# kbd.net
KiCad netlist of a schematic drawn in EAGLE
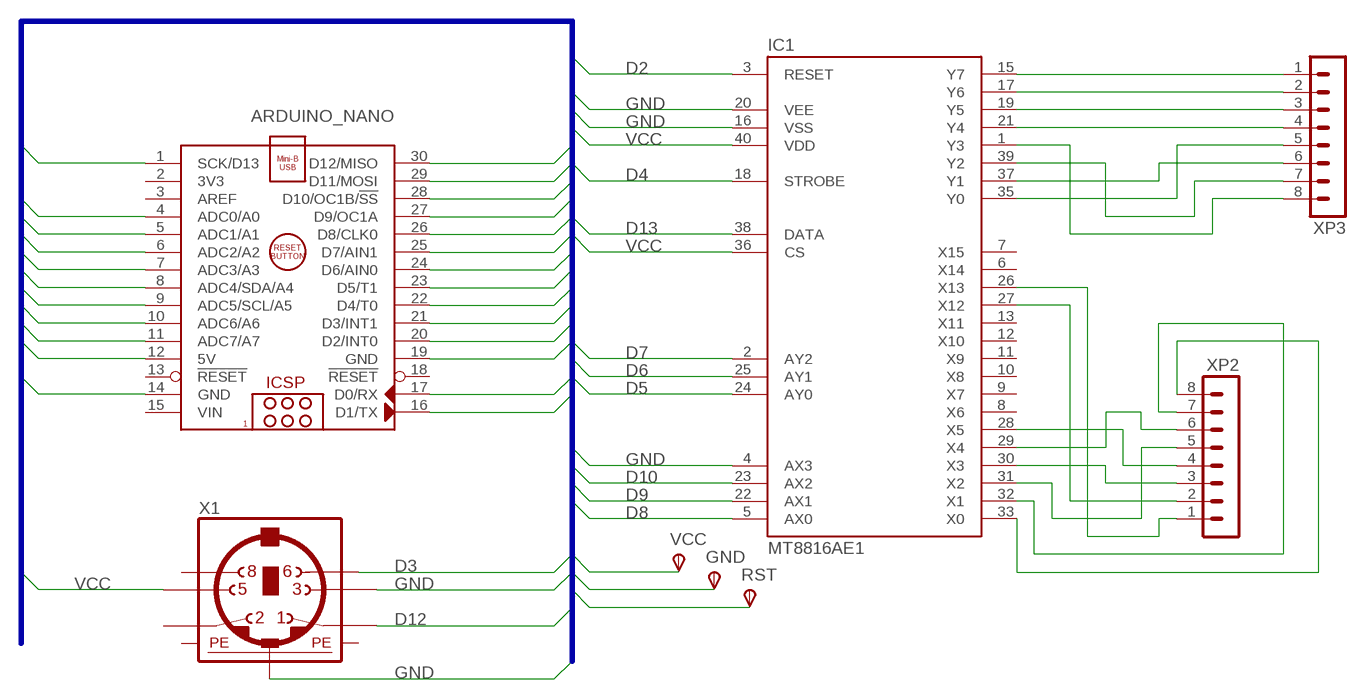
[diagram p0: schematic, sheet 1]

(export (version "E")
  (design (tool "Eeschema 10.0.6"))
  (components
    (comp (ref "ARDUINO_NANO")
      (value "ARDUINO_NANO")
      (footprint "eagle-import:ARDUINO_NANO")
      (libsource (lib "eagle-import") (part "ARDUINO_NANO"))
    )
    (comp (ref "GND")
      (value "TPSPAD1-13")
      (footprint "eagle-import:P1-13")
      (libsource (lib "eagle-import") (part "TPSPAD1-13"))
    )
    (comp (ref "IC1")
      (value "MT8816AE1")
      (footprint "eagle-import:DIL40")
      (libsource (lib "eagle-import") (part "MT8816AE1"))
    )
    (comp (ref "RST")
      (value "TPSPAD1-13")
      (footprint "eagle-import:P1-13")
      (libsource (lib "eagle-import") (part "TPSPAD1-13"))
    )
    (comp (ref "VCC")
      (value "TPSPAD1-13")
      (footprint "eagle-import:P1-13")
      (libsource (lib "eagle-import") (part "TPSPAD1-13"))
    )
    (comp (ref "X1")
      (value "MINI_DIN_6")
      (footprint "eagle-import:M_DIN6")
      (libsource (lib "eagle-import") (part "MINI_DIN_6"))
    )
    (comp (ref "XP2")
      (value "MA08-1")
      (footprint "eagle-import:MA08-1")
      (libsource (lib "eagle-import") (part "MA08-1"))
    )
    (comp (ref "XP3")
      (value "MA08-1")
      (footprint "eagle-import:MA08-1")
      (libsource (lib "eagle-import") (part "MA08-1"))
    )
  )
  (nets
    (net (code "1") (name "/A0") (class "Default")
      (node (ref "ARDUINO_NANO") (pin "4") (pinfunction "ADC0/A0_4") (pintype "bidirectional"))
      (node (ref "RST") (pin "TP") (pinfunction "PP_TP") (pintype "input"))
    )
    (net (code "2") (name "/D2") (class "Default")
      (node (ref "ARDUINO_NANO") (pin "20") (pinfunction "D2/INT0_20") (pintype "bidirectional"))
      (node (ref "IC1") (pin "3") (pinfunction "RESET_3") (pintype "input"))
    )
    (net (code "3") (name "/D3") (class "Default")
      (node (ref "ARDUINO_NANO") (pin "21") (pinfunction "D3/INT1_21") (pintype "bidirectional"))
      (node (ref "X1") (pin "6") (pinfunction "6_6") (pintype "passive"))
    )
    (net (code "4") (name "/D4") (class "Default")
      (node (ref "ARDUINO_NANO") (pin "22") (pinfunction "D4/T0_22") (pintype "bidirectional"))
      (node (ref "IC1") (pin "18") (pinfunction "STROBE_18") (pintype "input"))
    )
    (net (code "5") (name "/D5") (class "Default")
      (node (ref "ARDUINO_NANO") (pin "23") (pinfunction "D5/T1_23") (pintype "bidirectional"))
      (node (ref "IC1") (pin "24") (pinfunction "AY0_24") (pintype "input"))
    )
    (net (code "6") (name "/D6") (class "Default")
      (node (ref "ARDUINO_NANO") (pin "24") (pinfunction "D6/AIN0_24") (pintype "bidirectional"))
      (node (ref "IC1") (pin "25") (pinfunction "AY1_25") (pintype "input"))
    )
    (net (code "7") (name "/D7") (class "Default")
      (node (ref "ARDUINO_NANO") (pin "25") (pinfunction "D7/AIN1_25") (pintype "bidirectional"))
      (node (ref "IC1") (pin "2") (pinfunction "AY2_2") (pintype "input"))
    )
    (net (code "8") (name "/D8") (class "Default")
      (node (ref "ARDUINO_NANO") (pin "26") (pinfunction "D8/CLK0_26") (pintype "bidirectional"))
      (node (ref "IC1") (pin "5") (pinfunction "AX0_5") (pintype "input"))
    )
    (net (code "9") (name "/D9") (class "Default")
      (node (ref "ARDUINO_NANO") (pin "27") (pinfunction "D9/OC1A_27") (pintype "bidirectional"))
      (node (ref "IC1") (pin "22") (pinfunction "AX1_22") (pintype "input"))
    )
    (net (code "10") (name "/D10") (class "Default")
      (node (ref "ARDUINO_NANO") (pin "28") (pinfunction "D10/OC1B/~{SS}_28") (pintype "bidirectional"))
      (node (ref "IC1") (pin "23") (pinfunction "AX2_23") (pintype "input"))
    )
    (net (code "11") (name "/D12") (class "Default")
      (node (ref "ARDUINO_NANO") (pin "30") (pinfunction "D12/MISO_30") (pintype "bidirectional"))
      (node (ref "X1") (pin "1") (pinfunction "1_1") (pintype "passive"))
    )
    (net (code "12") (name "/D13") (class "Default")
      (node (ref "ARDUINO_NANO") (pin "1") (pinfunction "SCK/D13_1") (pintype "bidirectional"))
      (node (ref "IC1") (pin "38") (pinfunction "DATA_38") (pintype "input"))
    )
    (net (code "13") (name "/GND") (class "Default")
      (node (ref "ARDUINO_NANO") (pin "14") (pinfunction "GND_14") (pintype "power_in"))
      (node (ref "ARDUINO_NANO") (pin "19") (pinfunction "GND_19") (pintype "power_in"))
      (node (ref "GND") (pin "TP") (pinfunction "PP_TP") (pintype "input"))
      (node (ref "IC1") (pin "16") (pinfunction "VSS_16") (pintype "power_in"))
      (node (ref "IC1") (pin "20") (pinfunction "VEE_20") (pintype "power_in"))
      (node (ref "IC1") (pin "4") (pinfunction "AX3_4") (pintype "input"))
      (node (ref "X1") (pin "3") (pinfunction "3_3") (pintype "passive"))
      (node (ref "X1") (pin "SH2") (pinfunction "PE2_SH2") (pintype "power_in"))
    )
    (net (code "14") (name "/PE1") (class "Default")
      (node (ref "X1") (pin "SH1") (pinfunction "PE1_SH1") (pintype "power_in"))
    )
    (net (code "15") (name "/PE3") (class "Default")
      (node (ref "X1") (pin "SH3") (pinfunction "PE3_SH3") (pintype "power_in"))
    )
    (net (code "16") (name "/VCC") (class "Default")
      (node (ref "ARDUINO_NANO") (pin "12") (pinfunction "5V_12") (pintype "power_in"))
      (node (ref "IC1") (pin "36") (pinfunction "CS_36") (pintype "input"))
      (node (ref "IC1") (pin "40") (pinfunction "VDD_40") (pintype "power_in"))
      (node (ref "VCC") (pin "TP") (pinfunction "PP_TP") (pintype "input"))
      (node (ref "X1") (pin "5") (pinfunction "5_5") (pintype "passive"))
    )
    (net (code "17") (name "/VIN") (class "Default")
      (node (ref "ARDUINO_NANO") (pin "15") (pinfunction "VIN_15") (pintype "power_in"))
    )
    (net (code "18") (name "Net-(IC1-X0)") (class "Default")
      (node (ref "IC1") (pin "33") (pinfunction "X0_33") (pintype "bidirectional"))
      (node (ref "XP2") (pin "8") (pinfunction "8_8") (pintype "passive"))
    )
    (net (code "19") (name "Net-(IC1-X1)") (class "Default")
      (node (ref "IC1") (pin "32") (pinfunction "X1_32") (pintype "bidirectional"))
      (node (ref "XP2") (pin "7") (pinfunction "7_7") (pintype "passive"))
    )
    (net (code "20") (name "Net-(IC1-X2)") (class "Default")
      (node (ref "IC1") (pin "31") (pinfunction "X2_31") (pintype "bidirectional"))
      (node (ref "XP2") (pin "5") (pinfunction "5_5") (pintype "passive"))
    )
    (net (code "21") (name "Net-(IC1-X3)") (class "Default")
      (node (ref "IC1") (pin "30") (pinfunction "X3_30") (pintype "bidirectional"))
      (node (ref "XP2") (pin "3") (pinfunction "3_3") (pintype "passive"))
    )
    (net (code "22") (name "Net-(IC1-X4)") (class "Default")
      (node (ref "IC1") (pin "29") (pinfunction "X4_29") (pintype "bidirectional"))
      (node (ref "XP2") (pin "6") (pinfunction "6_6") (pintype "passive"))
    )
    (net (code "23") (name "Net-(IC1-X5)") (class "Default")
      (node (ref "IC1") (pin "28") (pinfunction "X5_28") (pintype "bidirectional"))
      (node (ref "XP2") (pin "4") (pinfunction "4_4") (pintype "passive"))
    )
    (net (code "24") (name "Net-(IC1-X12)") (class "Default")
      (node (ref "IC1") (pin "27") (pinfunction "X12_27") (pintype "bidirectional"))
      (node (ref "XP2") (pin "2") (pinfunction "2_2") (pintype "passive"))
    )
    (net (code "25") (name "Net-(IC1-X13)") (class "Default")
      (node (ref "IC1") (pin "26") (pinfunction "X13_26") (pintype "bidirectional"))
      (node (ref "XP2") (pin "1") (pinfunction "1_1") (pintype "passive"))
    )
    (net (code "26") (name "Net-(IC1-Y0)") (class "Default")
      (node (ref "IC1") (pin "35") (pinfunction "Y0_35") (pintype "bidirectional"))
      (node (ref "XP3") (pin "5") (pinfunction "5_5") (pintype "passive"))
    )
    (net (code "27") (name "Net-(IC1-Y1)") (class "Default")
      (node (ref "IC1") (pin "37") (pinfunction "Y1_37") (pintype "bidirectional"))
      (node (ref "XP3") (pin "6") (pinfunction "6_6") (pintype "passive"))
    )
    (net (code "28") (name "Net-(IC1-Y2)") (class "Default")
      (node (ref "IC1") (pin "39") (pinfunction "Y2_39") (pintype "bidirectional"))
      (node (ref "XP3") (pin "7") (pinfunction "7_7") (pintype "passive"))
    )
    (net (code "29") (name "Net-(IC1-Y3)") (class "Default")
      (node (ref "IC1") (pin "1") (pinfunction "Y3_1") (pintype "bidirectional"))
      (node (ref "XP3") (pin "8") (pinfunction "8_8") (pintype "passive"))
    )
    (net (code "30") (name "Net-(IC1-Y4)") (class "Default")
      (node (ref "IC1") (pin "21") (pinfunction "Y4_21") (pintype "bidirectional"))
      (node (ref "XP3") (pin "4") (pinfunction "4_4") (pintype "passive"))
    )
    (net (code "31") (name "Net-(IC1-Y5)") (class "Default")
      (node (ref "IC1") (pin "19") (pinfunction "Y5_19") (pintype "bidirectional"))
      (node (ref "XP3") (pin "3") (pinfunction "3_3") (pintype "passive"))
    )
    (net (code "32") (name "Net-(IC1-Y6)") (class "Default")
      (node (ref "IC1") (pin "17") (pinfunction "Y6_17") (pintype "bidirectional"))
      (node (ref "XP3") (pin "2") (pinfunction "2_2") (pintype "passive"))
    )
    (net (code "33") (name "Net-(IC1-Y7)") (class "Default")
      (node (ref "IC1") (pin "15") (pinfunction "Y7_15") (pintype "bidirectional"))
      (node (ref "XP3") (pin "1") (pinfunction "1_1") (pintype "passive"))
    )
    (net (code "34") (name "unconnected-(ARDUINO_NANO-3V3-Pad2)") (class "Default")
      (node (ref "ARDUINO_NANO") (pin "2") (pinfunction "3V3_2") (pintype "output"))
    )
    (net (code "35") (name "unconnected-(ARDUINO_NANO-ADC1{slash}A1-Pad5)") (class "Default")
      (node (ref "ARDUINO_NANO") (pin "5") (pinfunction "ADC1/A1_5") (pintype "bidirectional"))
    )
    (net (code "36") (name "unconnected-(ARDUINO_NANO-ADC2{slash}A2-Pad6)") (class "Default")
      (node (ref "ARDUINO_NANO") (pin "6") (pinfunction "ADC2/A2_6") (pintype "bidirectional"))
    )
    (net (code "37") (name "unconnected-(ARDUINO_NANO-ADC3{slash}A3-Pad7)") (class "Default")
      (node (ref "ARDUINO_NANO") (pin "7") (pinfunction "ADC3/A3_7") (pintype "bidirectional"))
    )
    (net (code "38") (name "unconnected-(ARDUINO_NANO-ADC4{slash}SDA{slash}A4-Pad8)") (class "Default")
      (node (ref "ARDUINO_NANO") (pin "8") (pinfunction "ADC4/SDA/A4_8") (pintype "bidirectional"))
    )
    (net (code "39") (name "unconnected-(ARDUINO_NANO-ADC5{slash}SCL{slash}A5-Pad9)") (class "Default")
      (node (ref "ARDUINO_NANO") (pin "9") (pinfunction "ADC5/SCL/A5_9") (pintype "bidirectional"))
    )
    (net (code "40") (name "unconnected-(ARDUINO_NANO-ADC6{slash}A6-Pad10)") (class "Default")
      (node (ref "ARDUINO_NANO") (pin "10") (pinfunction "ADC6/A6_10") (pintype "bidirectional"))
    )
    (net (code "41") (name "unconnected-(ARDUINO_NANO-ADC7{slash}A7-Pad11)") (class "Default")
      (node (ref "ARDUINO_NANO") (pin "11") (pinfunction "ADC7/A7_11") (pintype "bidirectional"))
    )
    (net (code "42") (name "unconnected-(ARDUINO_NANO-AREF-Pad3)") (class "Default")
      (node (ref "ARDUINO_NANO") (pin "3") (pinfunction "AREF_3") (pintype "input"))
    )
    (net (code "43") (name "unconnected-(ARDUINO_NANO-D0{slash}RX-Pad17)") (class "Default")
      (node (ref "ARDUINO_NANO") (pin "17") (pinfunction "D0/RX_17") (pintype "bidirectional"))
    )
    (net (code "44") (name "unconnected-(ARDUINO_NANO-D1{slash}TX-Pad16)") (class "Default")
      (node (ref "ARDUINO_NANO") (pin "16") (pinfunction "D1/TX_16") (pintype "bidirectional"))
    )
    (net (code "45") (name "unconnected-(ARDUINO_NANO-D11{slash}MOSI-Pad29)") (class "Default")
      (node (ref "ARDUINO_NANO") (pin "29") (pinfunction "D11/MOSI_29") (pintype "bidirectional"))
    )
    (net (code "46") (name "unconnected-(ARDUINO_NANO-~{RESET}-Pad13)") (class "Default")
      (node (ref "ARDUINO_NANO") (pin "13") (pinfunction "~{RESET}_13") (pintype "input"))
    )
    (net (code "47") (name "unconnected-(ARDUINO_NANO-~{RESET}-Pad18)") (class "Default")
      (node (ref "ARDUINO_NANO") (pin "18") (pinfunction "~{RESET}_18") (pintype "input"))
    )
    (net (code "48") (name "unconnected-(IC1-X6-Pad8)") (class "Default")
      (node (ref "IC1") (pin "8") (pinfunction "X6_8") (pintype "bidirectional"))
    )
    (net (code "49") (name "unconnected-(IC1-X7-Pad9)") (class "Default")
      (node (ref "IC1") (pin "9") (pinfunction "X7_9") (pintype "bidirectional"))
    )
    (net (code "50") (name "unconnected-(IC1-X8-Pad10)") (class "Default")
      (node (ref "IC1") (pin "10") (pinfunction "X8_10") (pintype "bidirectional"))
    )
    (net (code "51") (name "unconnected-(IC1-X9-Pad11)") (class "Default")
      (node (ref "IC1") (pin "11") (pinfunction "X9_11") (pintype "bidirectional"))
    )
    (net (code "52") (name "unconnected-(IC1-X10-Pad12)") (class "Default")
      (node (ref "IC1") (pin "12") (pinfunction "X10_12") (pintype "bidirectional"))
    )
    (net (code "53") (name "unconnected-(IC1-X11-Pad13)") (class "Default")
      (node (ref "IC1") (pin "13") (pinfunction "X11_13") (pintype "bidirectional"))
    )
    (net (code "54") (name "unconnected-(IC1-X14-Pad6)") (class "Default")
      (node (ref "IC1") (pin "6") (pinfunction "X14_6") (pintype "bidirectional"))
    )
    (net (code "55") (name "unconnected-(IC1-X15-Pad7)") (class "Default")
      (node (ref "IC1") (pin "7") (pinfunction "X15_7") (pintype "bidirectional"))
    )
    (net (code "56") (name "unconnected-(X1-Pad2)") (class "Default")
      (node (ref "X1") (pin "2") (pinfunction "2_2") (pintype "passive"))
    )
    (net (code "57") (name "unconnected-(X1-Pad8)") (class "Default")
      (node (ref "X1") (pin "8") (pinfunction "8_8") (pintype "passive"))
    )
  )
)
